# Schematic.net
KiCad netlist of a schematic drawn in Altium Designer
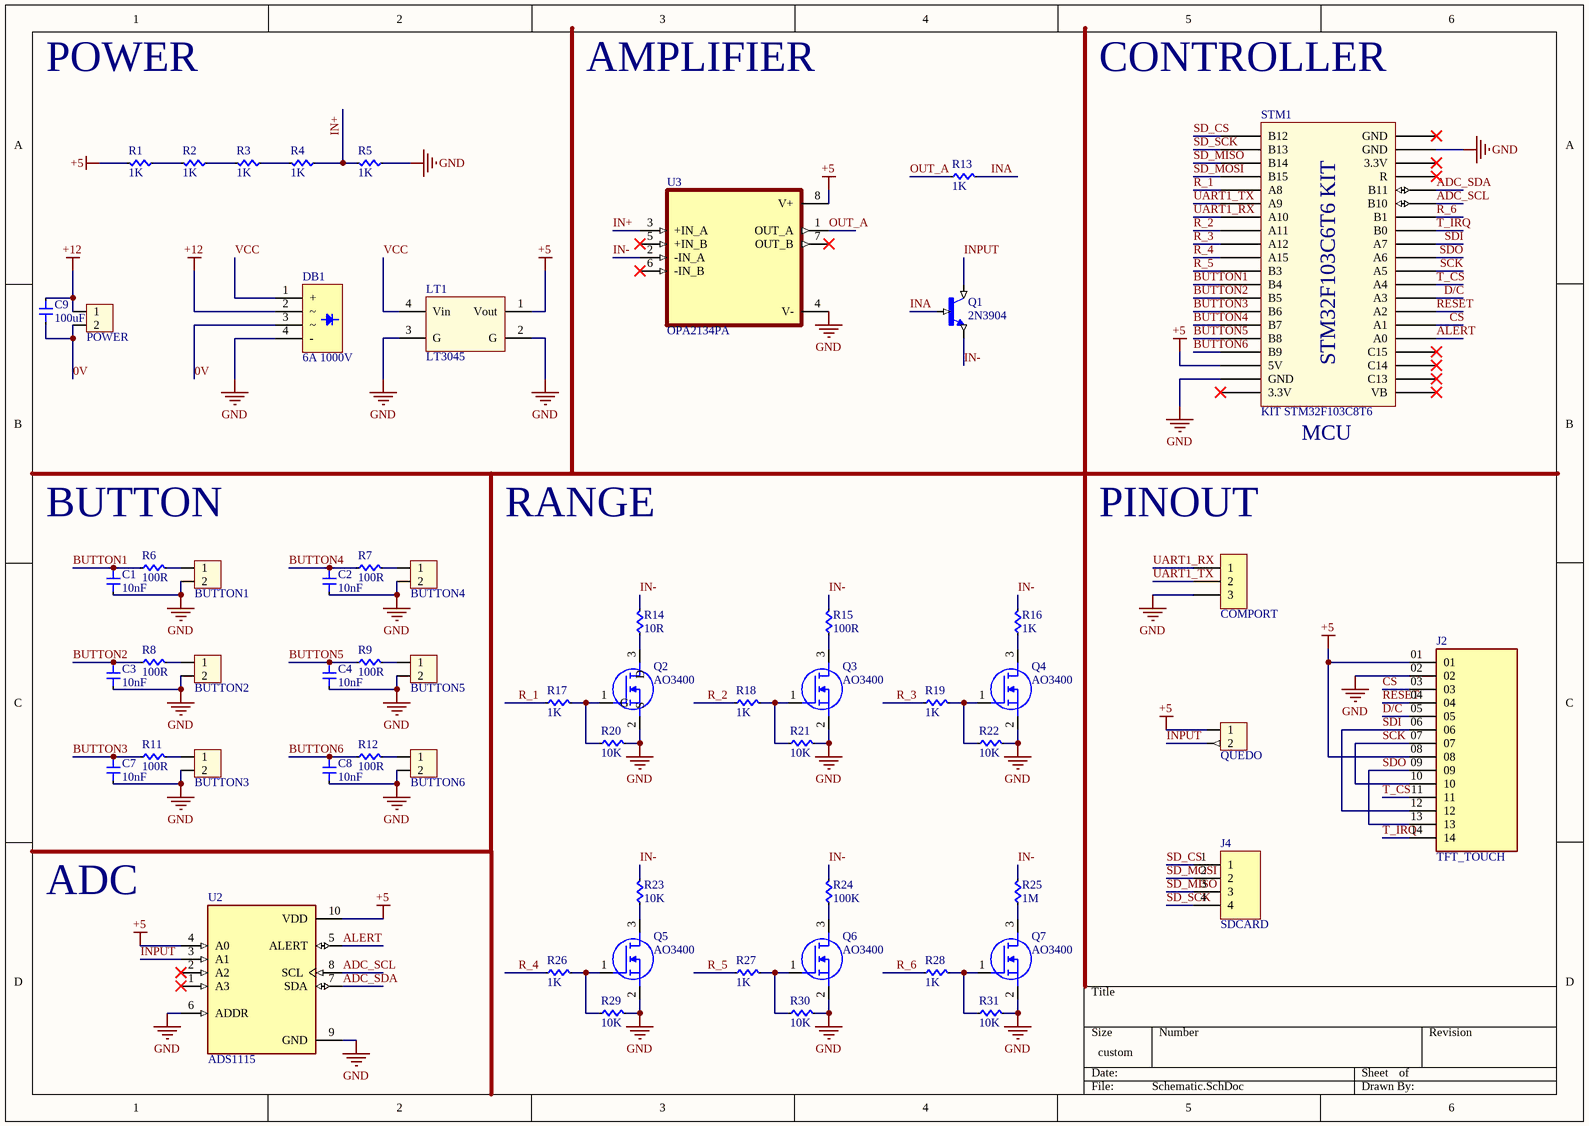
[diagram p0: Schematic.SchDoc]

(export (version "E")
  (design (tool "Eeschema 10.0.6"))
  (components
    (comp (ref "C1")
      (value "10nF")
      (footprint "Cap 1206")
      (description "Capacitor SMD 1206")
      (libsource (lib "KhueNguyenCreator") (part "Cap 1206"))
    )
    (comp (ref "C2")
      (value "10nF")
      (footprint "Cap 1206")
      (description "Capacitor SMD 1206")
      (libsource (lib "KhueNguyenCreator") (part "Cap 1206"))
    )
    (comp (ref "C3")
      (value "10nF")
      (footprint "Cap 1206")
      (description "Capacitor SMD 1206")
      (libsource (lib "KhueNguyenCreator") (part "Cap 1206"))
    )
    (comp (ref "C4")
      (value "10nF")
      (footprint "Cap 1206")
      (description "Capacitor SMD 1206")
      (libsource (lib "KhueNguyenCreator") (part "Cap 1206"))
    )
    (comp (ref "C7")
      (value "10nF")
      (footprint "Cap 1206")
      (description "Capacitor SMD 1206")
      (libsource (lib "KhueNguyenCreator") (part "Cap 1206"))
    )
    (comp (ref "C8")
      (value "10nF")
      (footprint "Cap 1206")
      (description "Capacitor SMD 1206")
      (libsource (lib "KhueNguyenCreator") (part "Cap 1206"))
    )
    (comp (ref "C9")
      (value "100uF")
      (footprint "Cap 1206")
      (description "Capacitor SMD 1206")
      (libsource (lib "KhueNguyenCreator") (part "Cap 1206"))
    )
    (comp (ref "DB1")
      (value "6A 1000V")
      (footprint "DIODE CAU 6A CAM")
      (description "Cắm")
      (libsource (lib "KhueNguyenCreator") (part "Diode CAU 6A"))
    )
    (comp (ref "H2")
      (value "POWER")
      (footprint "XH2.54M-2")
      (description "Cắm")
      (libsource (lib "KhueNguyenCreator") (part "Header 2P 2.54 Duc Thang"))
    )
    (comp (ref "H3")
      (value "BUTTON1")
      (footprint "XH2.54M-2")
      (description "Cắm")
      (libsource (lib "KhueNguyenCreator") (part "Header 2P 2.54 Duc Thang"))
    )
    (comp (ref "H4")
      (value "BUTTON4")
      (footprint "XH2.54M-2")
      (description "Cắm")
      (libsource (lib "KhueNguyenCreator") (part "Header 2P 2.54 Duc Thang"))
    )
    (comp (ref "H5")
      (value "BUTTON2")
      (footprint "XH2.54M-2")
      (description "Cắm")
      (libsource (lib "KhueNguyenCreator") (part "Header 2P 2.54 Duc Thang"))
    )
    (comp (ref "H6")
      (value "BUTTON5")
      (footprint "XH2.54M-2")
      (description "Cắm")
      (libsource (lib "KhueNguyenCreator") (part "Header 2P 2.54 Duc Thang"))
    )
    (comp (ref "H7")
      (value "BUTTON3")
      (footprint "XH2.54M-2")
      (description "Cắm")
      (libsource (lib "KhueNguyenCreator") (part "Header 2P 2.54 Duc Thang"))
    )
    (comp (ref "H8")
      (value "BUTTON6")
      (footprint "XH2.54M-2")
      (description "Cắm")
      (libsource (lib "KhueNguyenCreator") (part "Header 2P 2.54 Duc Thang"))
    )
    (comp (ref "H9")
      (value "COMPORT")
      (footprint "XH2.54M-3")
      (description "Cắm")
      (libsource (lib "KhueNguyenCreator") (part "Header 3P 2.54 Duc Thang"))
    )
    (comp (ref "H10")
      (value "QUEDO")
      (footprint "XH2.54M-2")
      (description "Cắm")
      (libsource (lib "KhueNguyenCreator") (part "Header 2P 2.54 Duc Thang"))
    )
    (comp (ref "J2")
      (value "TFT_TOUCH")
      (footprint "SAMTEC_ESQ-114-38-G-S")
      (fields (field (name "MP") "ESQ-114-38-G-S"))
      (libsource (lib "ESQ-114-38-G-S") (part "ESQ-114-38-G-S"))
    )
    (comp (ref "J4")
      (value "SDCARD")
      (footprint "CON4_78_B4B-PH-K-S(LF)(SN)")
      (description "Connector Header Through Hole 4 position 0.079\" (2.00mm)")
      (fields
        (field (name "MANUFACTURER PART NUMBER") "B4B-PH-K-S(LF)(SN)")
        (field (name "MANUFACTURER") "JST")
      )
      (libsource (lib "KhueNguyenCreator") (part "CON-PLG_4X1-78-ST-TH"))
    )
    (comp (ref "LT1")
      (value "LT3045")
      (footprint "PCBComponent_1")
      (libsource (lib "LT3045") (part "LT3045"))
    )
    (comp (ref "Q1")
      (value "2N3904")
      (footprint "TO92254P460H750-3")
      (description "BJT, TO-92, 40V, 200mA, NPN, 0.625W, 150Â°C")
      (fields (field (name "MF") "Diotec Semiconductor"))
      (libsource (lib "2N3904") (part "2N3904"))
    )
    (comp (ref "Q2")
      (value "AO3400")
      (footprint "SOT95P280X125-3N")
      (description "N-Channel 30 V 5.8A (Ta) 1.4W (Ta) Surface Mount SOT-23-3")
      (fields (field (name "MF") "Alpha &"))
      (libsource (lib "") (part "AO3400_1"))
    )
    (comp (ref "Q3")
      (value "AO3400")
      (footprint "SOT95P280X125-3N")
      (description "N-Channel 30 V 5.8A (Ta) 1.4W (Ta) Surface Mount SOT-23-3")
      (fields (field (name "MF") "Alpha &"))
      (libsource (lib "AO3400") (part "AO3400"))
    )
    (comp (ref "Q4")
      (value "AO3400")
      (footprint "SOT95P280X125-3N")
      (description "N-Channel 30 V 5.8A (Ta) 1.4W (Ta) Surface Mount SOT-23-3")
      (fields (field (name "MF") "Alpha &"))
      (libsource (lib "AO3400") (part "AO3400"))
    )
    (comp (ref "Q5")
      (value "AO3400")
      (footprint "SOT95P280X125-3N")
      (description "N-Channel 30 V 5.8A (Ta) 1.4W (Ta) Surface Mount SOT-23-3")
      (fields (field (name "MF") "Alpha &"))
      (libsource (lib "AO3400") (part "AO3400"))
    )
    (comp (ref "Q6")
      (value "AO3400")
      (footprint "SOT95P280X125-3N")
      (description "N-Channel 30 V 5.8A (Ta) 1.4W (Ta) Surface Mount SOT-23-3")
      (fields (field (name "MF") "Alpha &"))
      (libsource (lib "AO3400") (part "AO3400"))
    )
    (comp (ref "Q7")
      (value "AO3400")
      (footprint "SOT95P280X125-3N")
      (description "N-Channel 30 V 5.8A (Ta) 1.4W (Ta) Surface Mount SOT-23-3")
      (fields (field (name "MF") "Alpha &"))
      (libsource (lib "AO3400") (part "AO3400"))
    )
    (comp (ref "R1")
      (value "1K")
      (footprint "RES 1206")
      (description "RES SMD 1206")
      (fields
        (field (name "MANUFACTURER") "Vishay Dale")
        (field (name "MANUFACTURER PART NUMBER") "CRCW040210K0FKED")
      )
      (libsource (lib "KhueNguyenCreator") (part "RES 1206"))
    )
    (comp (ref "R2")
      (value "1K")
      (footprint "RES 1206")
      (description "RES SMD 1206")
      (fields
        (field (name "MANUFACTURER") "Vishay Dale")
        (field (name "MANUFACTURER PART NUMBER") "CRCW040210K0FKED")
      )
      (libsource (lib "KhueNguyenCreator") (part "RES 1206"))
    )
    (comp (ref "R3")
      (value "1K")
      (footprint "RES 1206")
      (description "RES SMD 1206")
      (fields
        (field (name "MANUFACTURER") "Vishay Dale")
        (field (name "MANUFACTURER PART NUMBER") "CRCW040210K0FKED")
      )
      (libsource (lib "KhueNguyenCreator") (part "RES 1206"))
    )
    (comp (ref "R4")
      (value "1K")
      (footprint "RES 1206")
      (description "RES SMD 1206")
      (fields
        (field (name "MANUFACTURER") "Vishay Dale")
        (field (name "MANUFACTURER PART NUMBER") "CRCW040210K0FKED")
      )
      (libsource (lib "KhueNguyenCreator") (part "RES 1206"))
    )
    (comp (ref "R5")
      (value "1K")
      (footprint "RES 1206")
      (description "RES SMD 1206")
      (fields
        (field (name "MANUFACTURER") "Vishay Dale")
        (field (name "MANUFACTURER PART NUMBER") "CRCW040210K0FKED")
      )
      (libsource (lib "KhueNguyenCreator") (part "RES 1206"))
    )
    (comp (ref "R6")
      (value "100R")
      (footprint "RES 1206")
      (description "RES SMD 1206")
      (fields
        (field (name "MANUFACTURER") "Vishay Dale")
        (field (name "MANUFACTURER PART NUMBER") "CRCW040210K0FKED")
      )
      (libsource (lib "KhueNguyenCreator") (part "RES 1206"))
    )
    (comp (ref "R7")
      (value "100R")
      (footprint "RES 1206")
      (description "RES SMD 1206")
      (fields
        (field (name "MANUFACTURER") "Vishay Dale")
        (field (name "MANUFACTURER PART NUMBER") "CRCW040210K0FKED")
      )
      (libsource (lib "KhueNguyenCreator") (part "RES 1206"))
    )
    (comp (ref "R8")
      (value "100R")
      (footprint "RES 1206")
      (description "RES SMD 1206")
      (fields
        (field (name "MANUFACTURER") "Vishay Dale")
        (field (name "MANUFACTURER PART NUMBER") "CRCW040210K0FKED")
      )
      (libsource (lib "KhueNguyenCreator") (part "RES 1206"))
    )
    (comp (ref "R9")
      (value "100R")
      (footprint "RES 1206")
      (description "RES SMD 1206")
      (fields
        (field (name "MANUFACTURER") "Vishay Dale")
        (field (name "MANUFACTURER PART NUMBER") "CRCW040210K0FKED")
      )
      (libsource (lib "KhueNguyenCreator") (part "RES 1206"))
    )
    (comp (ref "R11")
      (value "100R")
      (footprint "RES 1206")
      (description "RES SMD 1206")
      (fields
        (field (name "MANUFACTURER") "Vishay Dale")
        (field (name "MANUFACTURER PART NUMBER") "CRCW040210K0FKED")
      )
      (libsource (lib "KhueNguyenCreator") (part "RES 1206"))
    )
    (comp (ref "R12")
      (value "100R")
      (footprint "RES 1206")
      (description "RES SMD 1206")
      (fields
        (field (name "MANUFACTURER") "Vishay Dale")
        (field (name "MANUFACTURER PART NUMBER") "CRCW040210K0FKED")
      )
      (libsource (lib "KhueNguyenCreator") (part "RES 1206"))
    )
    (comp (ref "R13")
      (value "1K")
      (footprint "RES 1206")
      (description "RES SMD 1206")
      (fields
        (field (name "MANUFACTURER") "Vishay Dale")
        (field (name "MANUFACTURER PART NUMBER") "CRCW040210K0FKED")
      )
      (libsource (lib "KhueNguyenCreator") (part "RES 1206"))
    )
    (comp (ref "R14")
      (value "10R")
      (footprint "RES 1206")
      (description "RES SMD 1206")
      (fields
        (field (name "MANUFACTURER") "Vishay Dale")
        (field (name "MANUFACTURER PART NUMBER") "CRCW040210K0FKED")
      )
      (libsource (lib "KhueNguyenCreator") (part "RES 1206"))
    )
    (comp (ref "R15")
      (value "100R")
      (footprint "RES 1206")
      (description "RES SMD 1206")
      (fields
        (field (name "MANUFACTURER") "Vishay Dale")
        (field (name "MANUFACTURER PART NUMBER") "CRCW040210K0FKED")
      )
      (libsource (lib "KhueNguyenCreator") (part "RES 1206"))
    )
    (comp (ref "R16")
      (value "1K")
      (footprint "RES 1206")
      (description "RES SMD 1206")
      (fields
        (field (name "MANUFACTURER") "Vishay Dale")
        (field (name "MANUFACTURER PART NUMBER") "CRCW040210K0FKED")
      )
      (libsource (lib "KhueNguyenCreator") (part "RES 1206"))
    )
    (comp (ref "R17")
      (value "1K")
      (footprint "RES 1206")
      (description "RES SMD 1206")
      (fields
        (field (name "MANUFACTURER") "Vishay Dale")
        (field (name "MANUFACTURER PART NUMBER") "CRCW040210K0FKED")
      )
      (libsource (lib "KhueNguyenCreator") (part "RES 1206"))
    )
    (comp (ref "R18")
      (value "1K")
      (footprint "RES 1206")
      (description "RES SMD 1206")
      (fields
        (field (name "MANUFACTURER") "Vishay Dale")
        (field (name "MANUFACTURER PART NUMBER") "CRCW040210K0FKED")
      )
      (libsource (lib "KhueNguyenCreator") (part "RES 1206"))
    )
    (comp (ref "R19")
      (value "1K")
      (footprint "RES 1206")
      (description "RES SMD 1206")
      (fields
        (field (name "MANUFACTURER") "Vishay Dale")
        (field (name "MANUFACTURER PART NUMBER") "CRCW040210K0FKED")
      )
      (libsource (lib "KhueNguyenCreator") (part "RES 1206"))
    )
    (comp (ref "R20")
      (value "10K")
      (footprint "RES 1206")
      (description "RES SMD 1206")
      (fields
        (field (name "MANUFACTURER") "Vishay Dale")
        (field (name "MANUFACTURER PART NUMBER") "CRCW040210K0FKED")
      )
      (libsource (lib "KhueNguyenCreator") (part "RES 1206"))
    )
    (comp (ref "R21")
      (value "10K")
      (footprint "RES 1206")
      (description "RES SMD 1206")
      (fields
        (field (name "MANUFACTURER") "Vishay Dale")
        (field (name "MANUFACTURER PART NUMBER") "CRCW040210K0FKED")
      )
      (libsource (lib "KhueNguyenCreator") (part "RES 1206"))
    )
    (comp (ref "R22")
      (value "10K")
      (footprint "RES 1206")
      (description "RES SMD 1206")
      (fields
        (field (name "MANUFACTURER") "Vishay Dale")
        (field (name "MANUFACTURER PART NUMBER") "CRCW040210K0FKED")
      )
      (libsource (lib "KhueNguyenCreator") (part "RES 1206"))
    )
    (comp (ref "R23")
      (value "10K")
      (footprint "RES 1206")
      (description "RES SMD 1206")
      (fields
        (field (name "MANUFACTURER") "Vishay Dale")
        (field (name "MANUFACTURER PART NUMBER") "CRCW040210K0FKED")
      )
      (libsource (lib "KhueNguyenCreator") (part "RES 1206"))
    )
    (comp (ref "R24")
      (value "100K")
      (footprint "RES 1206")
      (description "RES SMD 1206")
      (fields
        (field (name "MANUFACTURER") "Vishay Dale")
        (field (name "MANUFACTURER PART NUMBER") "CRCW040210K0FKED")
      )
      (libsource (lib "KhueNguyenCreator") (part "RES 1206"))
    )
    (comp (ref "R25")
      (value "1M")
      (footprint "RES 1206")
      (description "RES SMD 1206")
      (fields
        (field (name "MANUFACTURER") "Vishay Dale")
        (field (name "MANUFACTURER PART NUMBER") "CRCW040210K0FKED")
      )
      (libsource (lib "KhueNguyenCreator") (part "RES 1206"))
    )
    (comp (ref "R26")
      (value "1K")
      (footprint "RES 1206")
      (description "RES SMD 1206")
      (fields
        (field (name "MANUFACTURER") "Vishay Dale")
        (field (name "MANUFACTURER PART NUMBER") "CRCW040210K0FKED")
      )
      (libsource (lib "KhueNguyenCreator") (part "RES 1206"))
    )
    (comp (ref "R27")
      (value "1K")
      (footprint "RES 1206")
      (description "RES SMD 1206")
      (fields
        (field (name "MANUFACTURER") "Vishay Dale")
        (field (name "MANUFACTURER PART NUMBER") "CRCW040210K0FKED")
      )
      (libsource (lib "KhueNguyenCreator") (part "RES 1206"))
    )
    (comp (ref "R28")
      (value "1K")
      (footprint "RES 1206")
      (description "RES SMD 1206")
      (fields
        (field (name "MANUFACTURER") "Vishay Dale")
        (field (name "MANUFACTURER PART NUMBER") "CRCW040210K0FKED")
      )
      (libsource (lib "KhueNguyenCreator") (part "RES 1206"))
    )
    (comp (ref "R29")
      (value "10K")
      (footprint "RES 1206")
      (description "RES SMD 1206")
      (fields
        (field (name "MANUFACTURER") "Vishay Dale")
        (field (name "MANUFACTURER PART NUMBER") "CRCW040210K0FKED")
      )
      (libsource (lib "KhueNguyenCreator") (part "RES 1206"))
    )
    (comp (ref "R30")
      (value "10K")
      (footprint "RES 1206")
      (description "RES SMD 1206")
      (fields
        (field (name "MANUFACTURER") "Vishay Dale")
        (field (name "MANUFACTURER PART NUMBER") "CRCW040210K0FKED")
      )
      (libsource (lib "KhueNguyenCreator") (part "RES 1206"))
    )
    (comp (ref "R31")
      (value "10K")
      (footprint "RES 1206")
      (description "RES SMD 1206")
      (fields
        (field (name "MANUFACTURER") "Vishay Dale")
        (field (name "MANUFACTURER PART NUMBER") "CRCW040210K0FKED")
      )
      (libsource (lib "KhueNguyenCreator") (part "RES 1206"))
    )
    (comp (ref "STM1")
      (value "KIT STM32F103C8T6")
      (footprint "STM32F103 KIT")
      (description "KIT STM32F103C8T6 Bluepill")
      (libsource (lib "KhueNguyenCreator") (part "STM32f103 Bluepill"))
    )
    (comp (ref "U2")
      (value "ADS1115")
      (footprint "MODULE_ZC261500")
      (description "ADS1115 Module ADC 4 channel with Pro Gain Amplifier for Arduino RPi")
      (fields (field (name "MP") "ZC261500") (field (name "MF") "YKS"))
      (libsource (lib "ZC261500") (part "ZC261500"))
    )
    (comp (ref "U3")
      (value "OPA2134PA")
      (footprint "DIP794W45P254L959H508Q8")
      (fields
        (field (name "MF") "Texas Instruments")
        (field (name "BUYPART") "https://www.snapeda.com/parts/OPA2134PA/Texas%20Instruments/view-part/621607/?ref=eda")
      )
      (libsource (lib "OPA2134PA") (part "OPA2134PA"))
    )
  )
  (nets
    (net (code "1") (name "+5") (class "Default")
      (node (ref "H10") (pin "1") (pinfunction "1_1") (pintype "passive"))
      (node (ref "J2") (pin "01") (pinfunction "01_01") (pintype "passive"))
      (node (ref "J2") (pin "08") (pinfunction "08_08") (pintype "passive"))
      (node (ref "LT1") (pin "1") (pinfunction "Vout_1") (pintype "power_in"))
      (node (ref "R1") (pin "2") (pinfunction "2_2") (pintype "passive"))
      (node (ref "STM1") (pin "18") (pinfunction "5V_18") (pintype "power_in"))
      (node (ref "U2") (pin "10") (pinfunction "VDD_10") (pintype "power_in"))
      (node (ref "U2") (pin "4") (pinfunction "A0_4") (pintype "input"))
      (node (ref "U3") (pin "8") (pinfunction "V+_8") (pintype "power_in"))
    )
    (net (code "2") (name "+12") (class "Default")
      (node (ref "C9") (pin "1") (pinfunction "1_1") (pintype "passive"))
      (node (ref "DB1") (pin "2") (pinfunction "~_2") (pintype "passive"))
      (node (ref "H2") (pin "1") (pinfunction "1_1") (pintype "passive"))
    )
    (net (code "3") (name "/0V") (class "Default")
      (node (ref "C9") (pin "2") (pinfunction "2_2") (pintype "passive"))
      (node (ref "DB1") (pin "3") (pinfunction "~_3") (pintype "passive"))
      (node (ref "H2") (pin "2") (pinfunction "2_2") (pintype "passive"))
    )
    (net (code "4") (name "/ADC_SCL") (class "Default")
      (node (ref "STM1") (pin "35") (pinfunction "B10_35") (pintype "bidirectional"))
      (node (ref "U2") (pin "8") (pinfunction "SCL_8") (pintype "input"))
    )
    (net (code "5") (name "/ADC_SDA") (class "Default")
      (node (ref "STM1") (pin "36") (pinfunction "B11_36") (pintype "bidirectional"))
      (node (ref "U2") (pin "7") (pinfunction "SDA_7") (pintype "bidirectional"))
    )
    (net (code "6") (name "/ALERT") (class "Default")
      (node (ref "STM1") (pin "25") (pinfunction "A0_25") (pintype "passive"))
      (node (ref "U2") (pin "5") (pinfunction "ALERT_5") (pintype "bidirectional"))
    )
    (net (code "7") (name "/BUTTON1") (class "Default")
      (node (ref "C1") (pin "1") (pinfunction "1_1") (pintype "passive"))
      (node (ref "R6") (pin "1") (pinfunction "1_1") (pintype "passive"))
      (node (ref "STM1") (pin "12") (pinfunction "B4_12") (pintype "passive"))
    )
    (net (code "8") (name "/BUTTON2") (class "Default")
      (node (ref "C3") (pin "1") (pinfunction "1_1") (pintype "passive"))
      (node (ref "R8") (pin "1") (pinfunction "1_1") (pintype "passive"))
      (node (ref "STM1") (pin "13") (pinfunction "B5_13") (pintype "passive"))
    )
    (net (code "9") (name "/BUTTON3") (class "Default")
      (node (ref "C7") (pin "1") (pinfunction "1_1") (pintype "passive"))
      (node (ref "R11") (pin "1") (pinfunction "1_1") (pintype "passive"))
      (node (ref "STM1") (pin "14") (pinfunction "B6_14") (pintype "passive"))
    )
    (net (code "10") (name "/BUTTON4") (class "Default")
      (node (ref "C2") (pin "1") (pinfunction "1_1") (pintype "passive"))
      (node (ref "R7") (pin "1") (pinfunction "1_1") (pintype "passive"))
      (node (ref "STM1") (pin "15") (pinfunction "B7_15") (pintype "passive"))
    )
    (net (code "11") (name "/BUTTON5") (class "Default")
      (node (ref "C4") (pin "1") (pinfunction "1_1") (pintype "passive"))
      (node (ref "R9") (pin "1") (pinfunction "1_1") (pintype "passive"))
      (node (ref "STM1") (pin "16") (pinfunction "B8_16") (pintype "passive"))
    )
    (net (code "12") (name "/BUTTON6") (class "Default")
      (node (ref "C8") (pin "1") (pinfunction "1_1") (pintype "passive"))
      (node (ref "R12") (pin "1") (pinfunction "1_1") (pintype "passive"))
      (node (ref "STM1") (pin "17") (pinfunction "B9_17") (pintype "passive"))
    )
    (net (code "13") (name "/CS") (class "Default")
      (node (ref "J2") (pin "03") (pinfunction "03_03") (pintype "passive"))
      (node (ref "STM1") (pin "26") (pinfunction "A1_26") (pintype "passive"))
    )
    (net (code "14") (name "/D{slash}C") (class "Default")
      (node (ref "J2") (pin "05") (pinfunction "05_05") (pintype "passive"))
      (node (ref "STM1") (pin "28") (pinfunction "A3_28") (pintype "passive"))
    )
    (net (code "15") (name "/IN+") (class "Default")
      (node (ref "R4") (pin "1") (pinfunction "1_1") (pintype "passive"))
      (node (ref "R5") (pin "2") (pinfunction "2_2") (pintype "passive"))
      (node (ref "U3") (pin "3") (pinfunction "+IN_A_3") (pintype "input"))
    )
    (net (code "16") (name "/IN-") (class "Default")
      (node (ref "Q1") (pin "1") (pinfunction "E_1") (pintype "output"))
      (node (ref "R14") (pin "2") (pinfunction "2_2") (pintype "passive"))
      (node (ref "R15") (pin "2") (pinfunction "2_2") (pintype "passive"))
      (node (ref "R16") (pin "2") (pinfunction "2_2") (pintype "passive"))
      (node (ref "R23") (pin "2") (pinfunction "2_2") (pintype "passive"))
      (node (ref "R24") (pin "2") (pinfunction "2_2") (pintype "passive"))
      (node (ref "R25") (pin "2") (pinfunction "2_2") (pintype "passive"))
      (node (ref "U3") (pin "2") (pinfunction "-IN_A_2") (pintype "input"))
    )
    (net (code "17") (name "/INA") (class "Default")
      (node (ref "Q1") (pin "2") (pinfunction "B_2") (pintype "input"))
      (node (ref "R13") (pin "2") (pinfunction "2_2") (pintype "passive"))
    )
    (net (code "18") (name "/INPUT") (class "Default")
      (node (ref "H10") (pin "2") (pinfunction "2_2") (pintype "passive"))
      (node (ref "Q1") (pin "3") (pinfunction "C_3") (pintype "input"))
      (node (ref "U2") (pin "3") (pinfunction "A1_3") (pintype "input"))
    )
    (net (code "19") (name "/OUT_A") (class "Default")
      (node (ref "R13") (pin "1") (pinfunction "1_1") (pintype "passive"))
      (node (ref "U3") (pin "1") (pinfunction "OUT_A_1") (pintype "output"))
    )
    (net (code "20") (name "/RESET") (class "Default")
      (node (ref "J2") (pin "04") (pinfunction "04_04") (pintype "passive"))
      (node (ref "STM1") (pin "27") (pinfunction "A2_27") (pintype "passive"))
    )
    (net (code "21") (name "/R_1") (class "Default")
      (node (ref "R17") (pin "1") (pinfunction "1_1") (pintype "passive"))
      (node (ref "STM1") (pin "5") (pinfunction "A8_5") (pintype "passive"))
    )
    (net (code "22") (name "/R_2") (class "Default")
      (node (ref "R18") (pin "1") (pinfunction "1_1") (pintype "passive"))
      (node (ref "STM1") (pin "8") (pinfunction "A11_8") (pintype "passive"))
    )
    (net (code "23") (name "/R_3") (class "Default")
      (node (ref "R19") (pin "1") (pinfunction "1_1") (pintype "passive"))
      (node (ref "STM1") (pin "9") (pinfunction "A12_9") (pintype "passive"))
    )
    (net (code "24") (name "/R_4") (class "Default")
      (node (ref "R26") (pin "1") (pinfunction "1_1") (pintype "passive"))
      (node (ref "STM1") (pin "10") (pinfunction "A15_10") (pintype "passive"))
    )
    (net (code "25") (name "/R_5") (class "Default")
      (node (ref "R27") (pin "1") (pinfunction "1_1") (pintype "passive"))
      (node (ref "STM1") (pin "11") (pinfunction "B3_11") (pintype "passive"))
    )
    (net (code "26") (name "/R_6") (class "Default")
      (node (ref "R28") (pin "1") (pinfunction "1_1") (pintype "passive"))
      (node (ref "STM1") (pin "34") (pinfunction "B1_34") (pintype "passive"))
    )
    (net (code "27") (name "/SCK") (class "Default")
      (node (ref "J2") (pin "07") (pinfunction "07_07") (pintype "passive"))
      (node (ref "J2") (pin "10") (pinfunction "10_10") (pintype "passive"))
      (node (ref "STM1") (pin "30") (pinfunction "A5_30") (pintype "passive"))
    )
    (net (code "28") (name "/SDI") (class "Default")
      (node (ref "J2") (pin "06") (pinfunction "06_06") (pintype "passive"))
      (node (ref "J2") (pin "12") (pinfunction "12_12") (pintype "passive"))
      (node (ref "STM1") (pin "32") (pinfunction "A7_32") (pintype "passive"))
    )
    (net (code "29") (name "/SDO") (class "Default")
      (node (ref "J2") (pin "09") (pinfunction "09_09") (pintype "passive"))
      (node (ref "J2") (pin "13") (pinfunction "13_13") (pintype "passive"))
      (node (ref "STM1") (pin "31") (pinfunction "A6_31") (pintype "passive"))
    )
    (net (code "30") (name "/SD_CS") (class "Default")
      (node (ref "J4") (pin "1") (pinfunction "1_1") (pintype "passive"))
      (node (ref "STM1") (pin "1") (pinfunction "B12_1") (pintype "passive"))
    )
    (net (code "31") (name "/SD_MISO") (class "Default")
      (node (ref "J4") (pin "3") (pinfunction "3_3") (pintype "passive"))
      (node (ref "STM1") (pin "3") (pinfunction "B14_3") (pintype "passive"))
    )
    (net (code "32") (name "/SD_MOSI") (class "Default")
      (node (ref "J4") (pin "2") (pinfunction "2_2") (pintype "passive"))
      (node (ref "STM1") (pin "4") (pinfunction "B15_4") (pintype "passive"))
    )
    (net (code "33") (name "/SD_SCK") (class "Default")
      (node (ref "J4") (pin "4") (pinfunction "4_4") (pintype "passive"))
      (node (ref "STM1") (pin "2") (pinfunction "B13_2") (pintype "passive"))
    )
    (net (code "34") (name "/T_CS") (class "Default")
      (node (ref "J2") (pin "11") (pinfunction "11_11") (pintype "passive"))
      (node (ref "STM1") (pin "29") (pinfunction "A4_29") (pintype "passive"))
    )
    (net (code "35") (name "/T_IRQ") (class "Default")
      (node (ref "J2") (pin "14") (pinfunction "14_14") (pintype "passive"))
      (node (ref "STM1") (pin "33") (pinfunction "B0_33") (pintype "passive"))
    )
    (net (code "36") (name "/UART1_RX") (class "Default")
      (node (ref "H9") (pin "1") (pinfunction "1_1") (pintype "passive"))
      (node (ref "STM1") (pin "7") (pinfunction "A10_7") (pintype "passive"))
    )
    (net (code "37") (name "/UART1_TX") (class "Default")
      (node (ref "H9") (pin "2") (pinfunction "2_2") (pintype "passive"))
      (node (ref "STM1") (pin "6") (pinfunction "A9_6") (pintype "passive"))
    )
    (net (code "38") (name "/VCC") (class "Default")
      (node (ref "DB1") (pin "1") (pinfunction "+_1") (pintype "passive"))
      (node (ref "LT1") (pin "4") (pinfunction "Vin_4") (pintype "power_in"))
    )
    (net (code "39") (name "GND") (class "Default")
      (node (ref "C1") (pin "2") (pinfunction "2_2") (pintype "passive"))
      (node (ref "C2") (pin "2") (pinfunction "2_2") (pintype "passive"))
      (node (ref "C3") (pin "2") (pinfunction "2_2") (pintype "passive"))
      (node (ref "C4") (pin "2") (pinfunction "2_2") (pintype "passive"))
      (node (ref "C7") (pin "2") (pinfunction "2_2") (pintype "passive"))
      (node (ref "C8") (pin "2") (pinfunction "2_2") (pintype "passive"))
      (node (ref "DB1") (pin "4") (pinfunction "-_4") (pintype "passive"))
      (node (ref "H3") (pin "2") (pinfunction "2_2") (pintype "passive"))
      (node (ref "H4") (pin "2") (pinfunction "2_2") (pintype "passive"))
      (node (ref "H5") (pin "2") (pinfunction "2_2") (pintype "passive"))
      (node (ref "H6") (pin "2") (pinfunction "2_2") (pintype "passive"))
      (node (ref "H7") (pin "2") (pinfunction "2_2") (pintype "passive"))
      (node (ref "H8") (pin "2") (pinfunction "2_2") (pintype "passive"))
      (node (ref "H9") (pin "3") (pinfunction "3_3") (pintype "passive"))
      (node (ref "J2") (pin "02") (pinfunction "02_02") (pintype "passive"))
      (node (ref "LT1") (pin "2") (pinfunction "G_2") (pintype "power_in"))
      (node (ref "LT1") (pin "3") (pinfunction "G_3") (pintype "power_in"))
      (node (ref "Q2") (pin "2") (pinfunction "S_2") (pintype "power_in"))
      (node (ref "Q3") (pin "2") (pinfunction "S_2") (pintype "power_in"))
      (node (ref "Q4") (pin "2") (pinfunction "S_2") (pintype "power_in"))
      (node (ref "Q5") (pin "2") (pinfunction "S_2") (pintype "power_in"))
      (node (ref "Q6") (pin "2") (pinfunction "S_2") (pintype "power_in"))
      (node (ref "Q7") (pin "2") (pinfunction "S_2") (pintype "power_in"))
      (node (ref "R20") (pin "2") (pinfunction "2_2") (pintype "passive"))
      (node (ref "R21") (pin "2") (pinfunction "2_2") (pintype "passive"))
      (node (ref "R22") (pin "2") (pinfunction "2_2") (pintype "passive"))
      (node (ref "R29") (pin "2") (pinfunction "2_2") (pintype "passive"))
      (node (ref "R30") (pin "2") (pinfunction "2_2") (pintype "passive"))
      (node (ref "R31") (pin "2") (pinfunction "2_2") (pintype "passive"))
      (node (ref "R5") (pin "1") (pinfunction "1_1") (pintype "passive"))
      (node (ref "STM1") (pin "19") (pinfunction "GND_19") (pintype "power_in"))
      (node (ref "STM1") (pin "39") (pinfunction "GND_39") (pintype "power_in"))
      (node (ref "U2") (pin "6") (pinfunction "ADDR_6") (pintype "input"))
      (node (ref "U2") (pin "9") (pinfunction "GND_9") (pintype "power_in"))
      (node (ref "U3") (pin "4") (pinfunction "V-_4") (pintype "power_in"))
    )
    (net (code "40") (name "Net-(H3-Pad1)") (class "Default")
      (node (ref "H3") (pin "1") (pinfunction "1_1") (pintype "passive"))
      (node (ref "R6") (pin "2") (pinfunction "2_2") (pintype "passive"))
    )
    (net (code "41") (name "Net-(H4-Pad1)") (class "Default")
      (node (ref "H4") (pin "1") (pinfunction "1_1") (pintype "passive"))
      (node (ref "R7") (pin "2") (pinfunction "2_2") (pintype "passive"))
    )
    (net (code "42") (name "Net-(H5-Pad1)") (class "Default")
      (node (ref "H5") (pin "1") (pinfunction "1_1") (pintype "passive"))
      (node (ref "R8") (pin "2") (pinfunction "2_2") (pintype "passive"))
    )
    (net (code "43") (name "Net-(H6-Pad1)") (class "Default")
      (node (ref "H6") (pin "1") (pinfunction "1_1") (pintype "passive"))
      (node (ref "R9") (pin "2") (pinfunction "2_2") (pintype "passive"))
    )
    (net (code "44") (name "Net-(H7-Pad1)") (class "Default")
      (node (ref "H7") (pin "1") (pinfunction "1_1") (pintype "passive"))
      (node (ref "R11") (pin "2") (pinfunction "2_2") (pintype "passive"))
    )
    (net (code "45") (name "Net-(H8-Pad1)") (class "Default")
      (node (ref "H8") (pin "1") (pinfunction "1_1") (pintype "passive"))
      (node (ref "R12") (pin "2") (pinfunction "2_2") (pintype "passive"))
    )
    (net (code "46") (name "Net-(Q2-D)") (class "Default")
      (node (ref "Q2") (pin "3") (pinfunction "D_3") (pintype "bidirectional"))
      (node (ref "R14") (pin "1") (pinfunction "1_1") (pintype "passive"))
    )
    (net (code "47") (name "Net-(Q2-G)") (class "Default")
      (node (ref "Q2") (pin "1") (pinfunction "G_1") (pintype "bidirectional"))
      (node (ref "R17") (pin "2") (pinfunction "2_2") (pintype "passive"))
      (node (ref "R20") (pin "1") (pinfunction "1_1") (pintype "passive"))
    )
    (net (code "48") (name "Net-(Q3-D)") (class "Default")
      (node (ref "Q3") (pin "3") (pinfunction "D_3") (pintype "bidirectional"))
      (node (ref "R15") (pin "1") (pinfunction "1_1") (pintype "passive"))
    )
    (net (code "49") (name "Net-(Q3-G)") (class "Default")
      (node (ref "Q3") (pin "1") (pinfunction "G_1") (pintype "bidirectional"))
      (node (ref "R18") (pin "2") (pinfunction "2_2") (pintype "passive"))
      (node (ref "R21") (pin "1") (pinfunction "1_1") (pintype "passive"))
    )
    (net (code "50") (name "Net-(Q4-D)") (class "Default")
      (node (ref "Q4") (pin "3") (pinfunction "D_3") (pintype "bidirectional"))
      (node (ref "R16") (pin "1") (pinfunction "1_1") (pintype "passive"))
    )
    (net (code "51") (name "Net-(Q4-G)") (class "Default")
      (node (ref "Q4") (pin "1") (pinfunction "G_1") (pintype "bidirectional"))
      (node (ref "R19") (pin "2") (pinfunction "2_2") (pintype "passive"))
      (node (ref "R22") (pin "1") (pinfunction "1_1") (pintype "passive"))
    )
    (net (code "52") (name "Net-(Q5-D)") (class "Default")
      (node (ref "Q5") (pin "3") (pinfunction "D_3") (pintype "bidirectional"))
      (node (ref "R23") (pin "1") (pinfunction "1_1") (pintype "passive"))
    )
    (net (code "53") (name "Net-(Q5-G)") (class "Default")
      (node (ref "Q5") (pin "1") (pinfunction "G_1") (pintype "bidirectional"))
      (node (ref "R26") (pin "2") (pinfunction "2_2") (pintype "passive"))
      (node (ref "R29") (pin "1") (pinfunction "1_1") (pintype "passive"))
    )
    (net (code "54") (name "Net-(Q6-D)") (class "Default")
      (node (ref "Q6") (pin "3") (pinfunction "D_3") (pintype "bidirectional"))
      (node (ref "R24") (pin "1") (pinfunction "1_1") (pintype "passive"))
    )
    (net (code "55") (name "Net-(Q6-G)") (class "Default")
      (node (ref "Q6") (pin "1") (pinfunction "G_1") (pintype "bidirectional"))
      (node (ref "R27") (pin "2") (pinfunction "2_2") (pintype "passive"))
      (node (ref "R30") (pin "1") (pinfunction "1_1") (pintype "passive"))
    )
    (net (code "56") (name "Net-(Q7-D)") (class "Default")
      (node (ref "Q7") (pin "3") (pinfunction "D_3") (pintype "bidirectional"))
      (node (ref "R25") (pin "1") (pinfunction "1_1") (pintype "passive"))
    )
    (net (code "57") (name "Net-(Q7-G)") (class "Default")
      (node (ref "Q7") (pin "1") (pinfunction "G_1") (pintype "bidirectional"))
      (node (ref "R28") (pin "2") (pinfunction "2_2") (pintype "passive"))
      (node (ref "R31") (pin "1") (pinfunction "1_1") (pintype "passive"))
    )
    (net (code "58") (name "Net-(R1-Pad1)") (class "Default")
      (node (ref "R1") (pin "1") (pinfunction "1_1") (pintype "passive"))
      (node (ref "R2") (pin "2") (pinfunction "2_2") (pintype "passive"))
    )
    (net (code "59") (name "Net-(R2-Pad1)") (class "Default")
      (node (ref "R2") (pin "1") (pinfunction "1_1") (pintype "passive"))
      (node (ref "R3") (pin "2") (pinfunction "2_2") (pintype "passive"))
    )
    (net (code "60") (name "Net-(R3-Pad1)") (class "Default")
      (node (ref "R3") (pin "1") (pinfunction "1_1") (pintype "passive"))
      (node (ref "R4") (pin "2") (pinfunction "2_2") (pintype "passive"))
    )
    (net (code "61") (name "unconnected-(STM1-3.3V-Pad20)") (class "Default")
      (node (ref "STM1") (pin "20") (pinfunction "3.3V_20") (pintype "power_in+no_connect"))
    )
    (net (code "62") (name "unconnected-(STM1-3.3V-Pad38)") (class "Default")
      (node (ref "STM1") (pin "38") (pinfunction "3.3V_38") (pintype "power_in+no_connect"))
    )
    (net (code "63") (name "unconnected-(STM1-C13-Pad22)") (class "Default")
      (node (ref "STM1") (pin "22") (pinfunction "C13_22") (pintype "passive+no_connect"))
    )
    (net (code "64") (name "unconnected-(STM1-C14-Pad23)") (class "Default")
      (node (ref "STM1") (pin "23") (pinfunction "C14_23") (pintype "passive+no_connect"))
    )
    (net (code "65") (name "unconnected-(STM1-C15-Pad24)") (class "Default")
      (node (ref "STM1") (pin "24") (pinfunction "C15_24") (pintype "passive+no_connect"))
    )
    (net (code "66") (name "unconnected-(STM1-GND-Pad40)") (class "Default")
      (node (ref "STM1") (pin "40") (pinfunction "GND_40") (pintype "power_in+no_connect"))
    )
    (net (code "67") (name "unconnected-(STM1-R-Pad37)") (class "Default")
      (node (ref "STM1") (pin "37") (pinfunction "R_37") (pintype "passive+no_connect"))
    )
    (net (code "68") (name "unconnected-(STM1-VB-Pad21)") (class "Default")
      (node (ref "STM1") (pin "21") (pinfunction "VB_21") (pintype "power_in+no_connect"))
    )
    (net (code "69") (name "unconnected-(U2-A2-Pad2)") (class "Default")
      (node (ref "U2") (pin "2") (pinfunction "A2_2") (pintype "input+no_connect"))
    )
    (net (code "70") (name "unconnected-(U2-A3-Pad1)") (class "Default")
      (node (ref "U2") (pin "1") (pinfunction "A3_1") (pintype "input+no_connect"))
    )
    (net (code "71") (name "unconnected-(U3-+IN_B-Pad5)") (class "Default")
      (node (ref "U3") (pin "5") (pinfunction "+IN_B_5") (pintype "input+no_connect"))
    )
    (net (code "72") (name "unconnected-(U3--IN_B-Pad6)") (class "Default")
      (node (ref "U3") (pin "6") (pinfunction "-IN_B_6") (pintype "input+no_connect"))
    )
    (net (code "73") (name "unconnected-(U3-OUT_B-Pad7)") (class "Default")
      (node (ref "U3") (pin "7") (pinfunction "OUT_B_7") (pintype "output+no_connect"))
    )
  )
)
